# EncoderAdapter.net
KiCad netlist of a schematic drawn in EAGLE
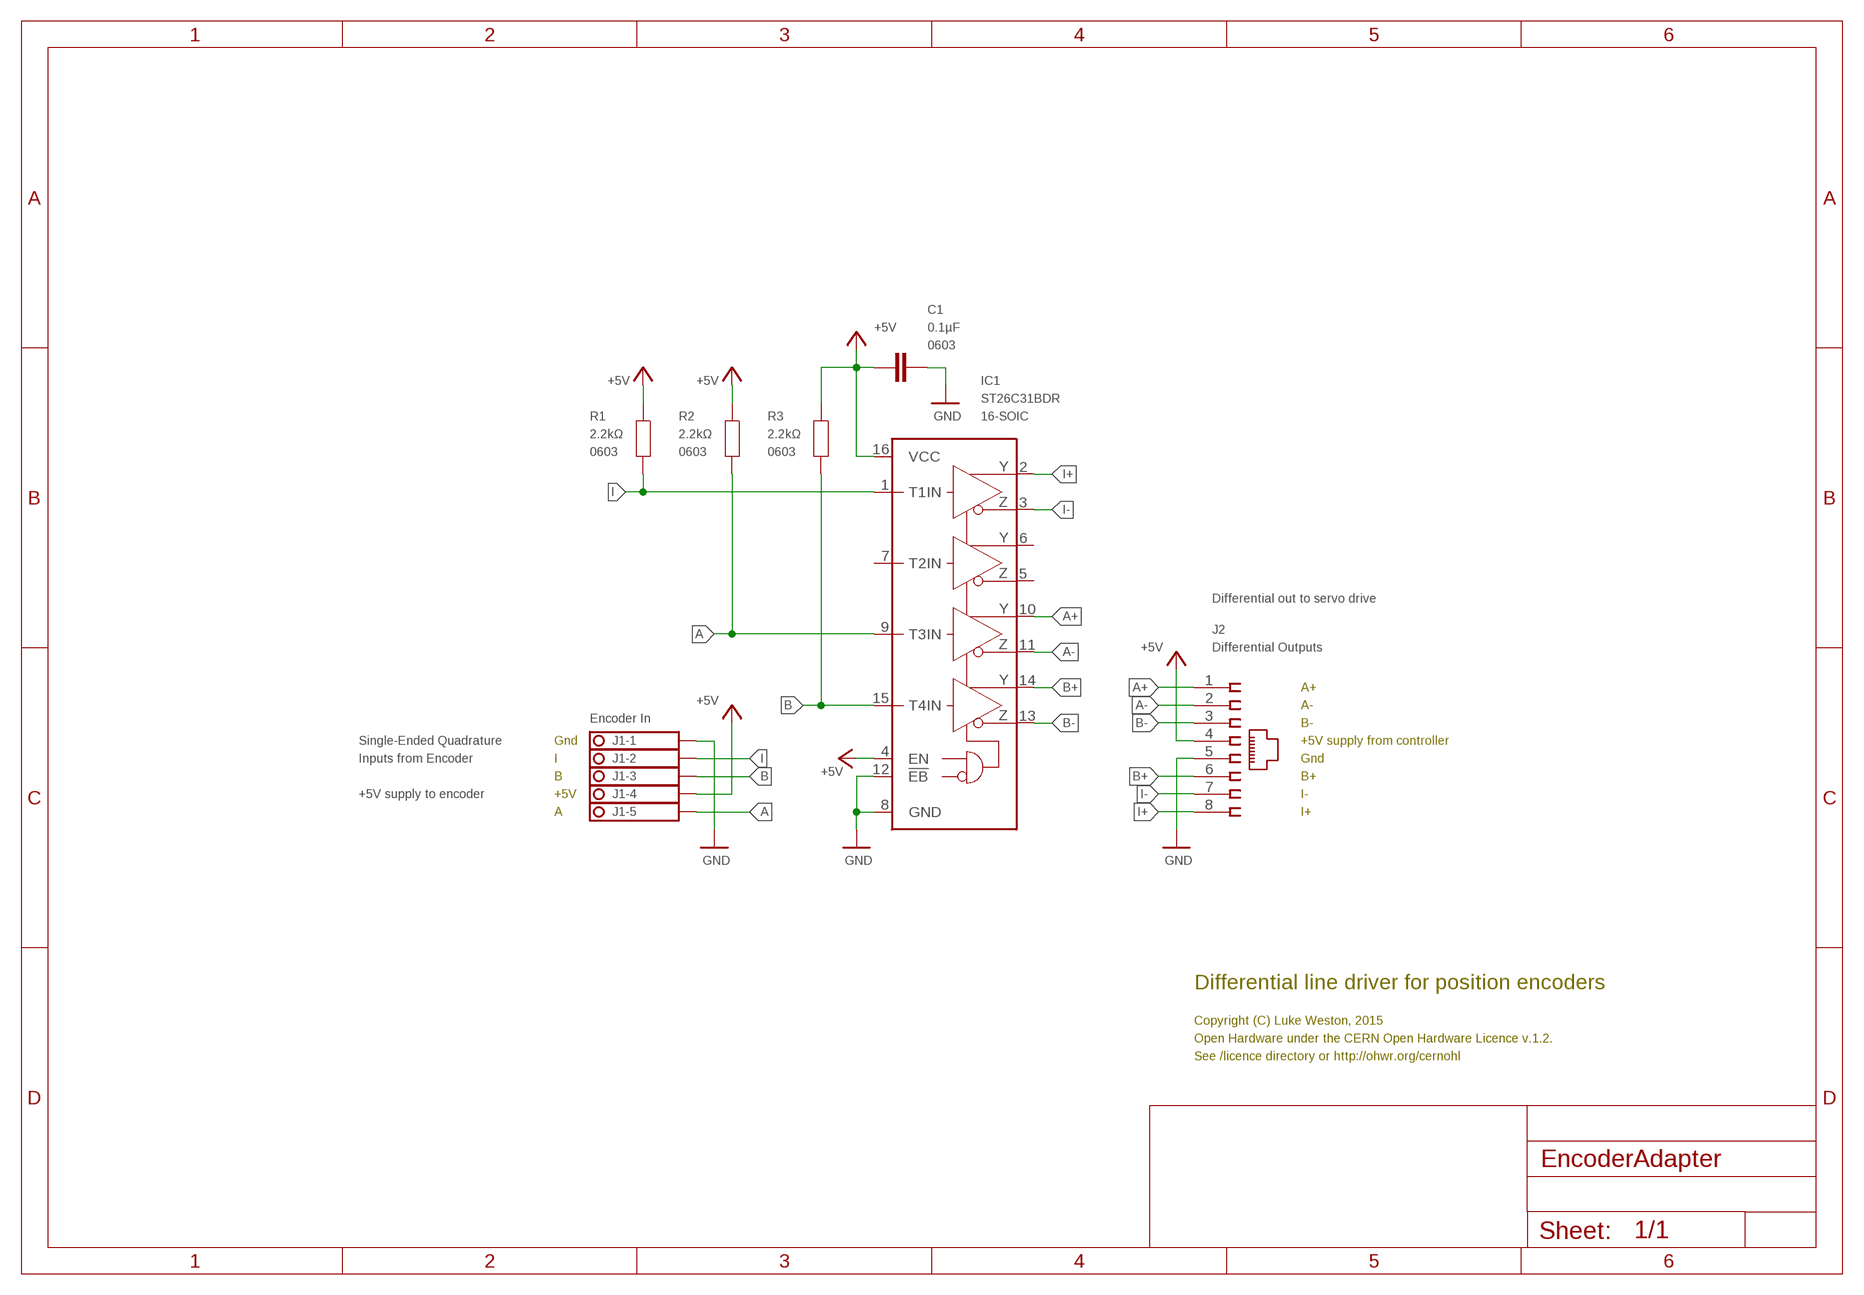
[diagram p0: schematic, sheet 1]

(export (version "E")
  (design (tool "Eeschema 10.0.6"))
  (components
    (comp (ref "C1")
      (value "0.1µF")
      (footprint "eagle-import:0603")
      (fields (field (name "PACKAGE") "0603"))
      (libsource (lib "eagle-import") (part "CAP0603"))
    )
    (comp (ref "IC1")
      (value "ST26C31BDR")
      (footprint "eagle-import:SO16")
      (fields
        (field (name "MF") "MAXIM")
        (field (name "MPN") "MAX3043CSE+")
        (field (name "PACKAGE") "16-SOIC")
      )
      (libsource (lib "eagle-import") (part "MAX304SE3C"))
    )
    (comp (ref "J1")
      (value "Encoder In")
      (footprint "eagle-import:1751277")
      (libsource (lib "eagle-import") (part "1751277"))
    )
    (comp (ref "J2")
      (value "Differential Outputs")
      (footprint "eagle-import:215877-4")
      (libsource (lib "eagle-import") (part "215877-4"))
    )
    (comp (ref "R1")
      (value "2.2kΩ")
      (footprint "eagle-import:0603")
      (fields (field (name "PACKAGE") "0603"))
      (libsource (lib "eagle-import") (part "RESISTOR0603"))
    )
    (comp (ref "R2")
      (value "2.2kΩ")
      (footprint "eagle-import:0603")
      (fields (field (name "PACKAGE") "0603"))
      (libsource (lib "eagle-import") (part "RESISTOR0603"))
    )
    (comp (ref "R3")
      (value "2.2kΩ")
      (footprint "eagle-import:0603")
      (fields (field (name "PACKAGE") "0603"))
      (libsource (lib "eagle-import") (part "RESISTOR0603"))
    )
  )
  (nets
    (net (code "1") (name "+5V") (class "Default")
      (node (ref "C1") (pin "2") (pinfunction "2_2") (pintype "passive"))
      (node (ref "IC1") (pin "16") (pinfunction "VCC_16") (pintype "power_in"))
      (node (ref "IC1") (pin "4") (pinfunction "EN_4") (pintype "input"))
      (node (ref "J1") (pin "4") (pinfunction "K_4") (pintype "passive"))
      (node (ref "J2") (pin "4") (pinfunction "4_4") (pintype "passive"))
      (node (ref "R1") (pin "1") (pinfunction "1_1") (pintype "passive"))
      (node (ref "R2") (pin "1") (pinfunction "1_1") (pintype "passive"))
      (node (ref "R3") (pin "1") (pinfunction "1_1") (pintype "passive"))
    )
    (net (code "2") (name "A") (class "Default")
      (node (ref "IC1") (pin "9") (pinfunction "T3IN_9") (pintype "input"))
      (node (ref "J1") (pin "5") (pinfunction "K_5") (pintype "passive"))
      (node (ref "R2") (pin "2") (pinfunction "2_2") (pintype "passive"))
    )
    (net (code "3") (name "A+") (class "Default")
      (node (ref "IC1") (pin "10") (pinfunction "Y3_10") (pintype "output"))
      (node (ref "J2") (pin "1") (pinfunction "1_1") (pintype "passive"))
    )
    (net (code "4") (name "A-") (class "Default")
      (node (ref "IC1") (pin "11") (pinfunction "Z3_11") (pintype "output"))
      (node (ref "J2") (pin "2") (pinfunction "2_2") (pintype "passive"))
    )
    (net (code "5") (name "B") (class "Default")
      (node (ref "IC1") (pin "15") (pinfunction "T4IN_15") (pintype "input"))
      (node (ref "J1") (pin "3") (pinfunction "K_3") (pintype "passive"))
      (node (ref "R3") (pin "2") (pinfunction "2_2") (pintype "passive"))
    )
    (net (code "6") (name "B+") (class "Default")
      (node (ref "IC1") (pin "14") (pinfunction "Y4_14") (pintype "output"))
      (node (ref "J2") (pin "6") (pinfunction "6_6") (pintype "passive"))
    )
    (net (code "7") (name "B-") (class "Default")
      (node (ref "IC1") (pin "13") (pinfunction "Z4_13") (pintype "output"))
      (node (ref "J2") (pin "3") (pinfunction "3_3") (pintype "passive"))
    )
    (net (code "8") (name "GND") (class "Default")
      (node (ref "C1") (pin "1") (pinfunction "1_1") (pintype "passive"))
      (node (ref "IC1") (pin "12") (pinfunction "~{EB}_12") (pintype "input"))
      (node (ref "IC1") (pin "8") (pinfunction "GND_8") (pintype "power_in"))
      (node (ref "J1") (pin "1") (pinfunction "K_1") (pintype "passive"))
      (node (ref "J2") (pin "5") (pinfunction "5_5") (pintype "passive"))
    )
    (net (code "9") (name "I") (class "Default")
      (node (ref "IC1") (pin "1") (pinfunction "T1IN_1") (pintype "input"))
      (node (ref "J1") (pin "2") (pinfunction "K_2") (pintype "passive"))
      (node (ref "R1") (pin "2") (pinfunction "2_2") (pintype "passive"))
    )
    (net (code "10") (name "I+") (class "Default")
      (node (ref "IC1") (pin "2") (pinfunction "Y1_2") (pintype "output"))
      (node (ref "J2") (pin "8") (pinfunction "8_8") (pintype "passive"))
    )
    (net (code "11") (name "I-") (class "Default")
      (node (ref "IC1") (pin "3") (pinfunction "Z1_3") (pintype "output"))
      (node (ref "J2") (pin "7") (pinfunction "7_7") (pintype "passive"))
    )
    (net (code "12") (name "unconnected-(IC1-T2IN-Pad7)") (class "Default")
      (node (ref "IC1") (pin "7") (pinfunction "T2IN_7") (pintype "input"))
    )
    (net (code "13") (name "unconnected-(IC1-Y2-Pad6)") (class "Default")
      (node (ref "IC1") (pin "6") (pinfunction "Y2_6") (pintype "output"))
    )
    (net (code "14") (name "unconnected-(IC1-Z2-Pad5)") (class "Default")
      (node (ref "IC1") (pin "5") (pinfunction "Z2_5") (pintype "output"))
    )
  )
)
